# Filter.net
KiCad netlist of a schematic drawn in EAGLE
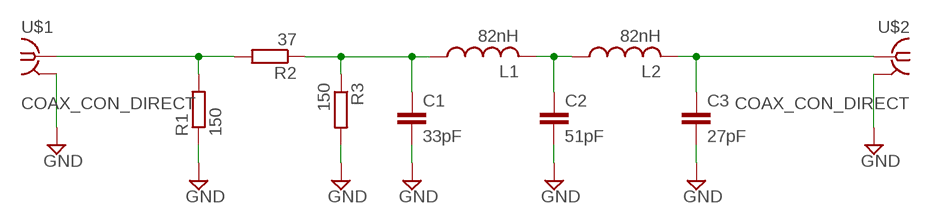
[diagram p0: schematic, sheet 1]

(export (version "E")
  (design (tool "Eeschema 10.0.6"))
  (components
    (comp (ref "C1")
      (value "33pF")
      (footprint "eagle-import:C0805")
      (libsource (lib "eagle-import") (part "C-EUC0805"))
    )
    (comp (ref "C2")
      (value "51pF")
      (footprint "eagle-import:C0805")
      (libsource (lib "eagle-import") (part "C-EUC0805"))
    )
    (comp (ref "C3")
      (value "27pF")
      (footprint "eagle-import:C0805")
      (libsource (lib "eagle-import") (part "C-EUC0805"))
    )
    (comp (ref "L1")
      (value "82nH")
      (footprint "eagle-import:L2012C")
      (libsource (lib "eagle-import") (part "L-USL2012C"))
    )
    (comp (ref "L2")
      (value "82nH")
      (footprint "eagle-import:L2012C")
      (libsource (lib "eagle-import") (part "L-USL2012C"))
    )
    (comp (ref "R1")
      (value "150")
      (footprint "eagle-import:R0805")
      (libsource (lib "eagle-import") (part "R-EU_R0805"))
    )
    (comp (ref "R2")
      (value "37")
      (footprint "eagle-import:R0805")
      (libsource (lib "eagle-import") (part "R-EU_R0805"))
    )
    (comp (ref "R3")
      (value "150")
      (footprint "eagle-import:R0805")
      (libsource (lib "eagle-import") (part "R-EU_R0805"))
    )
    (comp (ref "U$1")
      (value "COAX_CON_DIRECT")
      (footprint "eagle-import:COAX.141")
      (libsource (lib "eagle-import") (part "COAX_CON_DIRECT"))
    )
    (comp (ref "U$2")
      (value "COAX_CON_DIRECT")
      (footprint "eagle-import:COAX.141")
      (libsource (lib "eagle-import") (part "COAX_CON_DIRECT"))
    )
  )
  (nets
    (net (code "1") (name "GND") (class "Default")
      (node (ref "C1") (pin "2") (pinfunction "2_2") (pintype "passive"))
      (node (ref "C2") (pin "2") (pinfunction "2_2") (pintype "passive"))
      (node (ref "C3") (pin "2") (pinfunction "2_2") (pintype "passive"))
      (node (ref "R1") (pin "1") (pinfunction "1_1") (pintype "passive"))
      (node (ref "R3") (pin "2") (pinfunction "2_2") (pintype "passive"))
      (node (ref "U$1") (pin "P$2") (pinfunction "GND_P$2") (pintype "passive"))
      (node (ref "U$2") (pin "P$2") (pinfunction "GND_P$2") (pintype "passive"))
    )
    (net (code "2") (name "Net-(C1-Pad1)") (class "Default")
      (node (ref "C1") (pin "1") (pinfunction "1_1") (pintype "passive"))
      (node (ref "L1") (pin "1") (pinfunction "1_1") (pintype "passive"))
      (node (ref "R2") (pin "1") (pinfunction "1_1") (pintype "passive"))
      (node (ref "R3") (pin "1") (pinfunction "1_1") (pintype "passive"))
    )
    (net (code "3") (name "Net-(C2-Pad1)") (class "Default")
      (node (ref "C2") (pin "1") (pinfunction "1_1") (pintype "passive"))
      (node (ref "L1") (pin "2") (pinfunction "2_2") (pintype "passive"))
      (node (ref "L2") (pin "1") (pinfunction "1_1") (pintype "passive"))
    )
    (net (code "4") (name "Net-(U$1-1)") (class "Default")
      (node (ref "R1") (pin "2") (pinfunction "2_2") (pintype "passive"))
      (node (ref "R2") (pin "2") (pinfunction "2_2") (pintype "passive"))
      (node (ref "U$1") (pin "P$1") (pinfunction "1_P$1") (pintype "passive"))
    )
    (net (code "5") (name "Net-(U$2-1)") (class "Default")
      (node (ref "C3") (pin "1") (pinfunction "1_1") (pintype "passive"))
      (node (ref "L2") (pin "2") (pinfunction "2_2") (pintype "passive"))
      (node (ref "U$2") (pin "P$1") (pinfunction "1_P$1") (pintype "passive"))
    )
  )
)
